# LM2596.net
KiCad netlist of a schematic drawn in Altium Designer
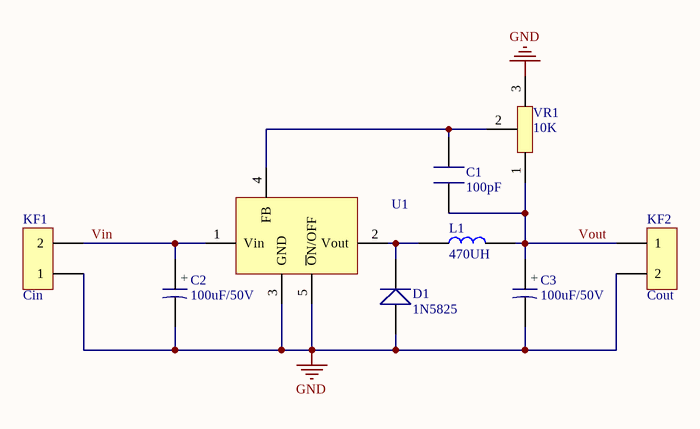
[diagram p0: LM2596.SchDoc]

(export (version "E")
  (design (tool "Eeschema 10.0.6"))
  (components
    (comp (ref "C1")
      (value "100pF")
      (footprint "C104 0603 SMD")
      (description "0603 SMD CAP")
      (libsource (lib "library") (part "C104 SMD"))
    )
    (comp (ref "C2")
      (value "100uF/50V")
      (footprint "UUD1H101MNL1GS")
      (description "CAP ALUM 100UF 50V SMD")
      (libsource (lib "library") (part "100uF/50V"))
    )
    (comp (ref "C3")
      (value "100uF/50V")
      (footprint "UUD1H101MNL1GS")
      (description "CAP ALUM 100UF 50V SMD")
      (libsource (lib "library") (part "100uF/50V"))
    )
    (comp (ref "D1")
      (value "1N5825")
      (footprint "SS34-SMA")
      (description "DIODE SCHOTTKY 3A 40V SMA")
      (libsource (lib "library") (part "Schottky 3A 40V SMA"))
    )
    (comp (ref "KF1")
      (value "Cin")
      (footprint "KF126")
      (description "2P-KF126 Domino")
      (libsource (lib "library") (part "KF2"))
    )
    (comp (ref "KF2")
      (value "Cout")
      (footprint "KF126")
      (description "2P-KF126 Domino")
      (libsource (lib "") (part "KF2_1"))
    )
    (comp (ref "L1")
      (value "470UH")
      (footprint "RH127-471")
      (description "470UH 0.79A, Size 12 x 12 x 8, SMD Inductor")
      (libsource (lib "library") (part "L SMD"))
    )
    (comp (ref "U1")
      (value "LM2596-ADJ")
      (footprint "TO263-5")
      (description "IC BUCK ADJ 3A TO263-5")
      (libsource (lib "library") (part "LM2596"))
    )
    (comp (ref "VR1") (value "10K") (footprint "RM065-203") (libsource (lib "library") (part "VR Res")))
  )
  (nets
    (net (code "1") (name "/Vin") (class "Default")
      (node (ref "C2") (pin "1") (pinfunction "+_1") (pintype "passive"))
      (node (ref "KF1") (pin "2") (pinfunction "2_2") (pintype "passive"))
      (node (ref "U1") (pin "1") (pinfunction "Vin_1") (pintype "passive"))
    )
    (net (code "2") (name "/Vout") (class "Default")
      (node (ref "C1") (pin "1") (pinfunction "1_1") (pintype "passive"))
      (node (ref "C3") (pin "1") (pinfunction "+_1") (pintype "passive"))
      (node (ref "KF2") (pin "1") (pinfunction "1_1") (pintype "passive"))
      (node (ref "L1") (pin "2") (pinfunction "2_2") (pintype "passive"))
      (node (ref "VR1") (pin "1") (pinfunction "1_1") (pintype "passive"))
    )
    (net (code "3") (name "GND") (class "Default")
      (node (ref "C2") (pin "2") (pinfunction "2_2") (pintype "passive"))
      (node (ref "C3") (pin "2") (pinfunction "2_2") (pintype "passive"))
      (node (ref "D1") (pin "1") (pinfunction "1_1") (pintype "passive"))
      (node (ref "KF1") (pin "1") (pinfunction "1_1") (pintype "passive"))
      (node (ref "KF2") (pin "2") (pinfunction "2_2") (pintype "passive"))
      (node (ref "U1") (pin "3") (pinfunction "GND_3") (pintype "passive"))
      (node (ref "U1") (pin "5") (pinfunction "~{O}N/OFF_5") (pintype "passive"))
      (node (ref "VR1") (pin "3") (pinfunction "3_3") (pintype "passive"))
    )
    (net (code "4") (name "Net-(U1-FB)") (class "Default")
      (node (ref "C1") (pin "2") (pinfunction "2_2") (pintype "passive"))
      (node (ref "U1") (pin "4") (pinfunction "FB_4") (pintype "passive"))
      (node (ref "VR1") (pin "2") (pinfunction "2_2") (pintype "passive"))
    )
    (net (code "5") (name "Net-(U1-Vout)") (class "Default")
      (node (ref "D1") (pin "2") (pinfunction "2_2") (pintype "passive"))
      (node (ref "L1") (pin "1") (pinfunction "1_1") (pintype "passive"))
      (node (ref "U1") (pin "2") (pinfunction "Vout_2") (pintype "passive"))
    )
  )
)
